# SCH_cligno-ESP32-C3_2025-02-09.net
KiCad netlist of a schematic drawn in EasyEDA
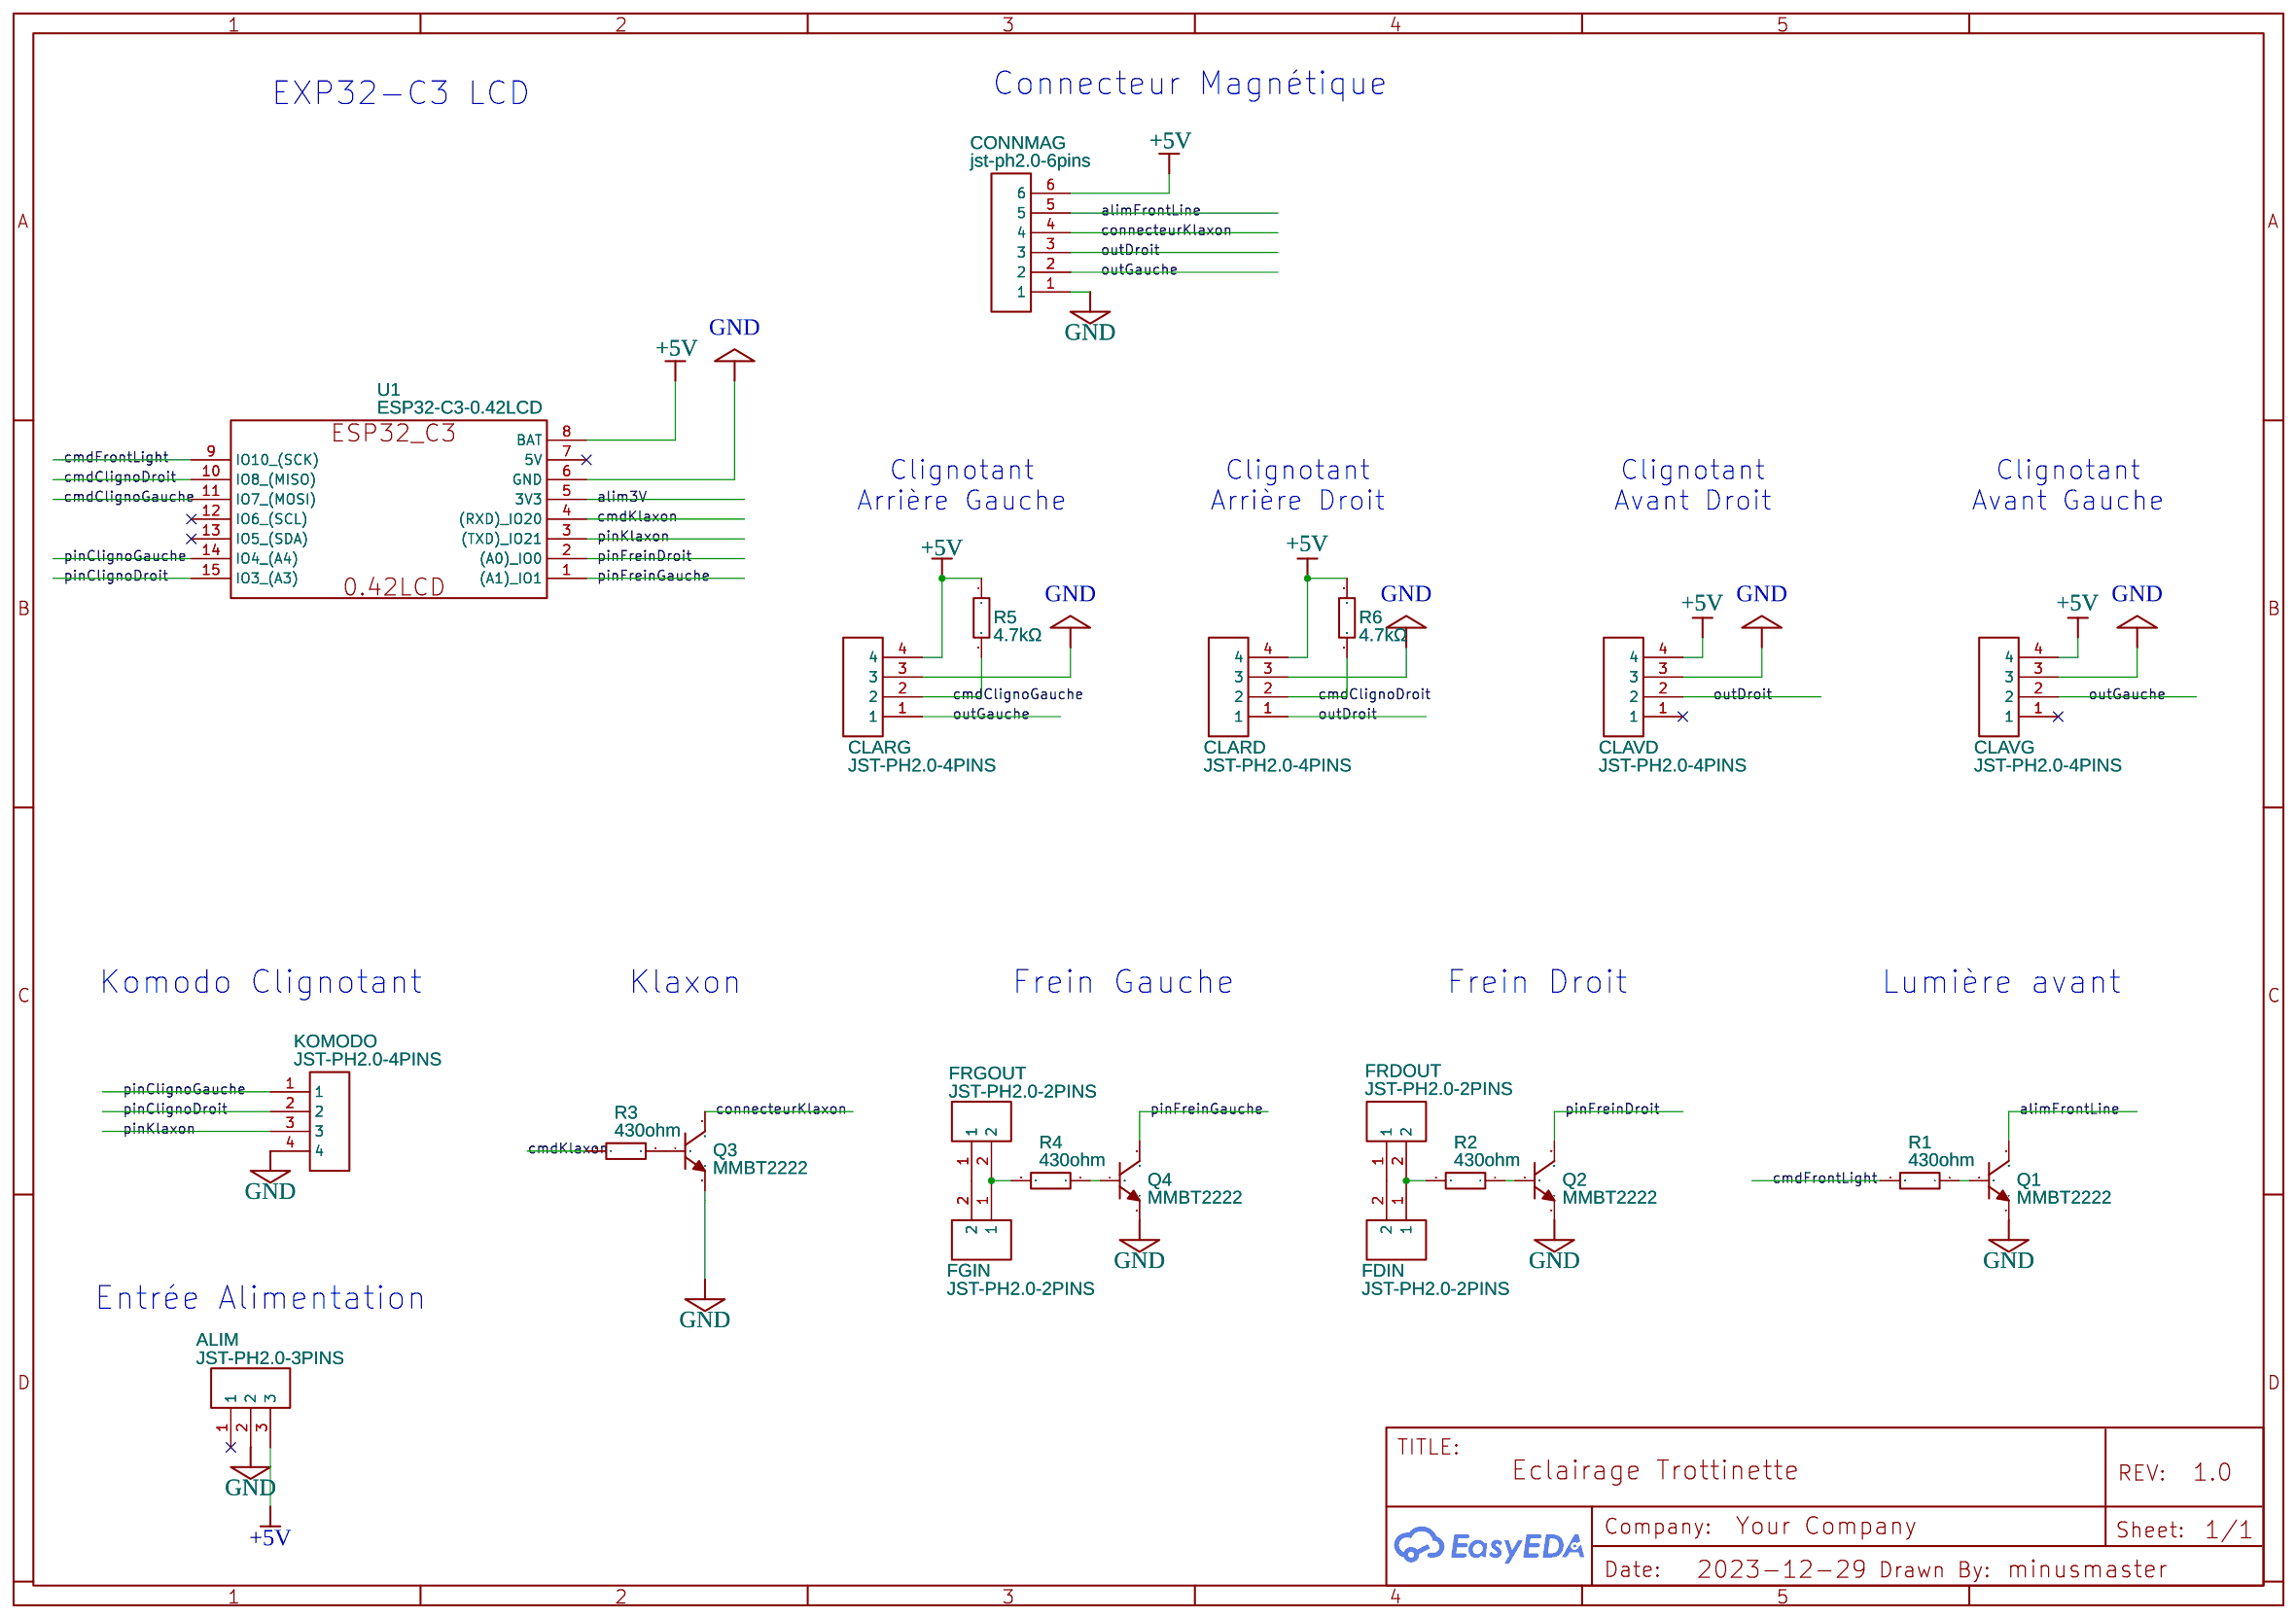
[diagram p0: schematic sheet]

(export (version "E")
  (design (tool "Eeschema 10.0.6"))
  (components
    (comp (ref "ALIM") (value "JST-PH2.0-3PINS") (libsource (lib "") (part "JST-PH2.0-3PINS")))
    (comp (ref "CLARD") (value "JST-PH2.0-4PINS") (libsource (lib "") (part "JST-PH2.0-4PINS_4")))
    (comp (ref "CLARG") (value "JST-PH2.0-4PINS") (libsource (lib "") (part "JST-PH2.0-4PINS_2")))
    (comp (ref "CLAVD") (value "JST-PH2.0-4PINS") (libsource (lib "") (part "JST-PH2.0-4PINS")))
    (comp (ref "CLAVG") (value "JST-PH2.0-4PINS") (libsource (lib "") (part "JST-PH2.0-4PINS_1")))
    (comp (ref "CONNMAG") (value "jst-ph2.0-6pins") (libsource (lib "") (part "jst-ph2.0-6pins")))
    (comp (ref "FDIN") (value "JST-PH2.0-2PINS") (libsource (lib "") (part "JST-PH2.0-2PINS")))
    (comp (ref "FGIN") (value "JST-PH2.0-2PINS") (libsource (lib "") (part "JST-PH2.0-2PINS_3")))
    (comp (ref "FRDOUT") (value "JST-PH2.0-2PINS") (libsource (lib "") (part "JST-PH2.0-2PINS_2")))
    (comp (ref "FRGOUT") (value "JST-PH2.0-2PINS") (libsource (lib "") (part "JST-PH2.0-2PINS_1")))
    (comp (ref "KOMODO") (value "JST-PH2.0-4PINS") (libsource (lib "") (part "JST-PH2.0-4PINS_3")))
    (comp (ref "Q1")
      (value "MMBT2222")
      (fields (field (name "Manufacturer") "YONGYUTAI(永裕泰)"))
      (libsource (lib "") (part "MMBT2222"))
    )
    (comp (ref "Q2")
      (value "MMBT2222")
      (fields (field (name "Manufacturer") "YONGYUTAI(永裕泰)"))
      (libsource (lib "") (part "MMBT2222"))
    )
    (comp (ref "Q3")
      (value "MMBT2222")
      (fields (field (name "Manufacturer") "YONGYUTAI(永裕泰)"))
      (libsource (lib "") (part "MMBT2222"))
    )
    (comp (ref "Q4")
      (value "MMBT2222")
      (fields (field (name "Manufacturer") "YONGYUTAI(永裕泰)"))
      (libsource (lib "") (part "MMBT2222"))
    )
    (comp (ref "R1")
      (value "430ohm")
      (fields (field (name "Manufacturer Part") "RMC12061205%N") (field (name "Manufacturer") "Tyohm(幸亚电阻)"))
      (libsource (lib "") (part "RMC12061205%N"))
    )
    (comp (ref "R2")
      (value "430ohm")
      (fields (field (name "Manufacturer Part") "RMC12061205%N") (field (name "Manufacturer") "Tyohm(幸亚电阻)"))
      (libsource (lib "") (part "RMC12061205%N"))
    )
    (comp (ref "R3")
      (value "430ohm")
      (fields (field (name "Manufacturer Part") "RMC12061205%N") (field (name "Manufacturer") "Tyohm(幸亚电阻)"))
      (libsource (lib "") (part "RMC12061205%N"))
    )
    (comp (ref "R4")
      (value "430ohm")
      (fields (field (name "Manufacturer Part") "RMC12061205%N") (field (name "Manufacturer") "Tyohm(幸亚电阻)"))
      (libsource (lib "") (part "RMC12061205%N"))
    )
    (comp (ref "R5")
      (value "4.7kΩ")
      (fields (field (name "Manufacturer Part") "RMC12061205%N") (field (name "Manufacturer") "Tyohm(幸亚电阻)"))
      (libsource (lib "") (part "RMC12061205%N_1"))
    )
    (comp (ref "R6")
      (value "4.7kΩ")
      (fields (field (name "Manufacturer Part") "RMC12061205%N") (field (name "Manufacturer") "Tyohm(幸亚电阻)"))
      (libsource (lib "") (part "RMC12061205%N_1"))
    )
    (comp (ref "U1") (value "ESP32-C3-0.42LCD") (libsource (lib "") (part "ESP32-C3-0.42LCD")))
  )
  (nets
    (net (code "1") (name "+5V") (class "Default")
      (node (ref "ALIM") (pin "3") (pinfunction "3_3") (pintype "unspecified"))
      (node (ref "CLARD") (pin "4") (pinfunction "4_4") (pintype "unspecified"))
      (node (ref "CLARG") (pin "4") (pinfunction "4_4") (pintype "unspecified"))
      (node (ref "CLAVD") (pin "4") (pinfunction "4_4") (pintype "unspecified"))
      (node (ref "CLAVG") (pin "4") (pinfunction "4_4") (pintype "unspecified"))
      (node (ref "CONNMAG") (pin "6") (pinfunction "6_6") (pintype "unspecified"))
      (node (ref "R5") (pin "1") (pinfunction "1_1") (pintype "unspecified"))
      (node (ref "R6") (pin "1") (pinfunction "1_1") (pintype "unspecified"))
      (node (ref "U1") (pin "8") (pinfunction "BAT_8") (pintype "unspecified"))
    )
    (net (code "2") (name "/alim3V") (class "Default")
      (node (ref "U1") (pin "5") (pinfunction "3V3_5") (pintype "unspecified"))
    )
    (net (code "3") (name "/alimFrontLine") (class "Default")
      (node (ref "CONNMAG") (pin "5") (pinfunction "5_5") (pintype "unspecified"))
      (node (ref "Q1") (pin "3") (pinfunction "C_3") (pintype "input"))
    )
    (net (code "4") (name "/cmdClignoDroit") (class "Default")
      (node (ref "CLARD") (pin "2") (pinfunction "2_2") (pintype "unspecified"))
      (node (ref "R6") (pin "2") (pinfunction "2_2") (pintype "unspecified"))
      (node (ref "U1") (pin "10") (pinfunction "IO8_(MISO)_10") (pintype "unspecified"))
    )
    (net (code "5") (name "/cmdClignoGauche") (class "Default")
      (node (ref "CLARG") (pin "2") (pinfunction "2_2") (pintype "unspecified"))
      (node (ref "R5") (pin "2") (pinfunction "2_2") (pintype "unspecified"))
      (node (ref "U1") (pin "11") (pinfunction "IO7_(MOSI)_11") (pintype "unspecified"))
    )
    (net (code "6") (name "/cmdFrontLight") (class "Default")
      (node (ref "R1") (pin "2") (pinfunction "2_2") (pintype "unspecified"))
      (node (ref "U1") (pin "9") (pinfunction "IO10_(SCK)_9") (pintype "unspecified"))
    )
    (net (code "7") (name "/cmdKlaxon") (class "Default")
      (node (ref "R3") (pin "2") (pinfunction "2_2") (pintype "unspecified"))
      (node (ref "U1") (pin "4") (pinfunction "(RXD)_IO20_4") (pintype "unspecified"))
    )
    (net (code "8") (name "/connecteurKlaxon") (class "Default")
      (node (ref "CONNMAG") (pin "4") (pinfunction "4_4") (pintype "unspecified"))
      (node (ref "Q3") (pin "3") (pinfunction "C_3") (pintype "input"))
    )
    (net (code "9") (name "/outDroit") (class "Default")
      (node (ref "CLARD") (pin "1") (pinfunction "1_1") (pintype "unspecified"))
      (node (ref "CLAVD") (pin "2") (pinfunction "2_2") (pintype "unspecified"))
      (node (ref "CONNMAG") (pin "3") (pinfunction "3_3") (pintype "unspecified"))
    )
    (net (code "10") (name "/outGauche") (class "Default")
      (node (ref "CLARG") (pin "1") (pinfunction "1_1") (pintype "unspecified"))
      (node (ref "CLAVG") (pin "2") (pinfunction "2_2") (pintype "unspecified"))
      (node (ref "CONNMAG") (pin "2") (pinfunction "2_2") (pintype "unspecified"))
    )
    (net (code "11") (name "/pinClignoDroit") (class "Default")
      (node (ref "KOMODO") (pin "2") (pinfunction "2_2") (pintype "unspecified"))
      (node (ref "U1") (pin "15") (pinfunction "IO3_(A3)_15") (pintype "unspecified"))
    )
    (net (code "12") (name "/pinClignoGauche") (class "Default")
      (node (ref "KOMODO") (pin "1") (pinfunction "1_1") (pintype "unspecified"))
      (node (ref "U1") (pin "14") (pinfunction "IO4_(A4)_14") (pintype "unspecified"))
    )
    (net (code "13") (name "/pinFreinDroit") (class "Default")
      (node (ref "Q2") (pin "3") (pinfunction "C_3") (pintype "input"))
      (node (ref "U1") (pin "2") (pinfunction "(A0)_IO0_2") (pintype "unspecified"))
    )
    (net (code "14") (name "/pinFreinGauche") (class "Default")
      (node (ref "Q4") (pin "3") (pinfunction "C_3") (pintype "input"))
      (node (ref "U1") (pin "1") (pinfunction "(A1)_IO1_1") (pintype "unspecified"))
    )
    (net (code "15") (name "/pinKlaxon") (class "Default")
      (node (ref "KOMODO") (pin "3") (pinfunction "3_3") (pintype "unspecified"))
      (node (ref "U1") (pin "3") (pinfunction "(TXD)_IO21_3") (pintype "unspecified"))
    )
    (net (code "16") (name "GND") (class "Default")
      (node (ref "ALIM") (pin "2") (pinfunction "2_2") (pintype "unspecified"))
      (node (ref "CLARD") (pin "3") (pinfunction "3_3") (pintype "unspecified"))
      (node (ref "CLARG") (pin "3") (pinfunction "3_3") (pintype "unspecified"))
      (node (ref "CLAVD") (pin "3") (pinfunction "3_3") (pintype "unspecified"))
      (node (ref "CLAVG") (pin "3") (pinfunction "3_3") (pintype "unspecified"))
      (node (ref "CONNMAG") (pin "1") (pinfunction "1_1") (pintype "unspecified"))
      (node (ref "KOMODO") (pin "4") (pinfunction "4_4") (pintype "unspecified"))
      (node (ref "Q1") (pin "2") (pinfunction "E_2") (pintype "input"))
      (node (ref "Q2") (pin "2") (pinfunction "E_2") (pintype "input"))
      (node (ref "Q3") (pin "2") (pinfunction "E_2") (pintype "input"))
      (node (ref "Q4") (pin "2") (pinfunction "E_2") (pintype "input"))
      (node (ref "U1") (pin "6") (pinfunction "GND_6") (pintype "unspecified"))
    )
    (net (code "17") (name "Net-(FDIN-Pad1)") (class "Default")
      (node (ref "FDIN") (pin "1") (pinfunction "1_1") (pintype "unspecified"))
      (node (ref "FRDOUT") (pin "2") (pinfunction "2_2") (pintype "unspecified"))
      (node (ref "R2") (pin "2") (pinfunction "2_2") (pintype "unspecified"))
    )
    (net (code "18") (name "Net-(FDIN-Pad2)") (class "Default")
      (node (ref "FDIN") (pin "2") (pinfunction "2_2") (pintype "unspecified"))
      (node (ref "FRDOUT") (pin "1") (pinfunction "1_1") (pintype "unspecified"))
    )
    (net (code "19") (name "Net-(FGIN-Pad1)") (class "Default")
      (node (ref "FGIN") (pin "1") (pinfunction "1_1") (pintype "unspecified"))
      (node (ref "FRGOUT") (pin "2") (pinfunction "2_2") (pintype "unspecified"))
      (node (ref "R4") (pin "2") (pinfunction "2_2") (pintype "unspecified"))
    )
    (net (code "20") (name "Net-(FGIN-Pad2)") (class "Default")
      (node (ref "FGIN") (pin "2") (pinfunction "2_2") (pintype "unspecified"))
      (node (ref "FRGOUT") (pin "1") (pinfunction "1_1") (pintype "unspecified"))
    )
    (net (code "21") (name "Net-(Q1-B)") (class "Default")
      (node (ref "Q1") (pin "1") (pinfunction "B_1") (pintype "input"))
      (node (ref "R1") (pin "1") (pinfunction "1_1") (pintype "unspecified"))
    )
    (net (code "22") (name "Net-(Q2-B)") (class "Default")
      (node (ref "Q2") (pin "1") (pinfunction "B_1") (pintype "input"))
      (node (ref "R2") (pin "1") (pinfunction "1_1") (pintype "unspecified"))
    )
    (net (code "23") (name "Net-(Q3-B)") (class "Default")
      (node (ref "Q3") (pin "1") (pinfunction "B_1") (pintype "input"))
      (node (ref "R3") (pin "1") (pinfunction "1_1") (pintype "unspecified"))
    )
    (net (code "24") (name "Net-(Q4-B)") (class "Default")
      (node (ref "Q4") (pin "1") (pinfunction "B_1") (pintype "input"))
      (node (ref "R4") (pin "1") (pinfunction "1_1") (pintype "unspecified"))
    )
    (net (code "25") (name "unconnected-(ALIM-Pad1)") (class "Default")
      (node (ref "ALIM") (pin "1") (pinfunction "1_1") (pintype "unspecified+no_connect"))
    )
    (net (code "26") (name "unconnected-(CLAVD-Pad1)") (class "Default")
      (node (ref "CLAVD") (pin "1") (pinfunction "1_1") (pintype "unspecified+no_connect"))
    )
    (net (code "27") (name "unconnected-(CLAVG-Pad1)") (class "Default")
      (node (ref "CLAVG") (pin "1") (pinfunction "1_1") (pintype "unspecified+no_connect"))
    )
    (net (code "28") (name "unconnected-(U1-5V-Pad7)") (class "Default")
      (node (ref "U1") (pin "7") (pinfunction "5V_7") (pintype "unspecified+no_connect"))
    )
    (net (code "29") (name "unconnected-(U1-IO5_(SDA)-Pad13)") (class "Default")
      (node (ref "U1") (pin "13") (pinfunction "IO5_(SDA)_13") (pintype "unspecified+no_connect"))
    )
    (net (code "30") (name "unconnected-(U1-IO6_(SCL)-Pad12)") (class "Default")
      (node (ref "U1") (pin "12") (pinfunction "IO6_(SCL)_12") (pintype "unspecified+no_connect"))
    )
  )
)
